# PowerAndController.net
KiCad netlist of a schematic drawn in Altium Designer
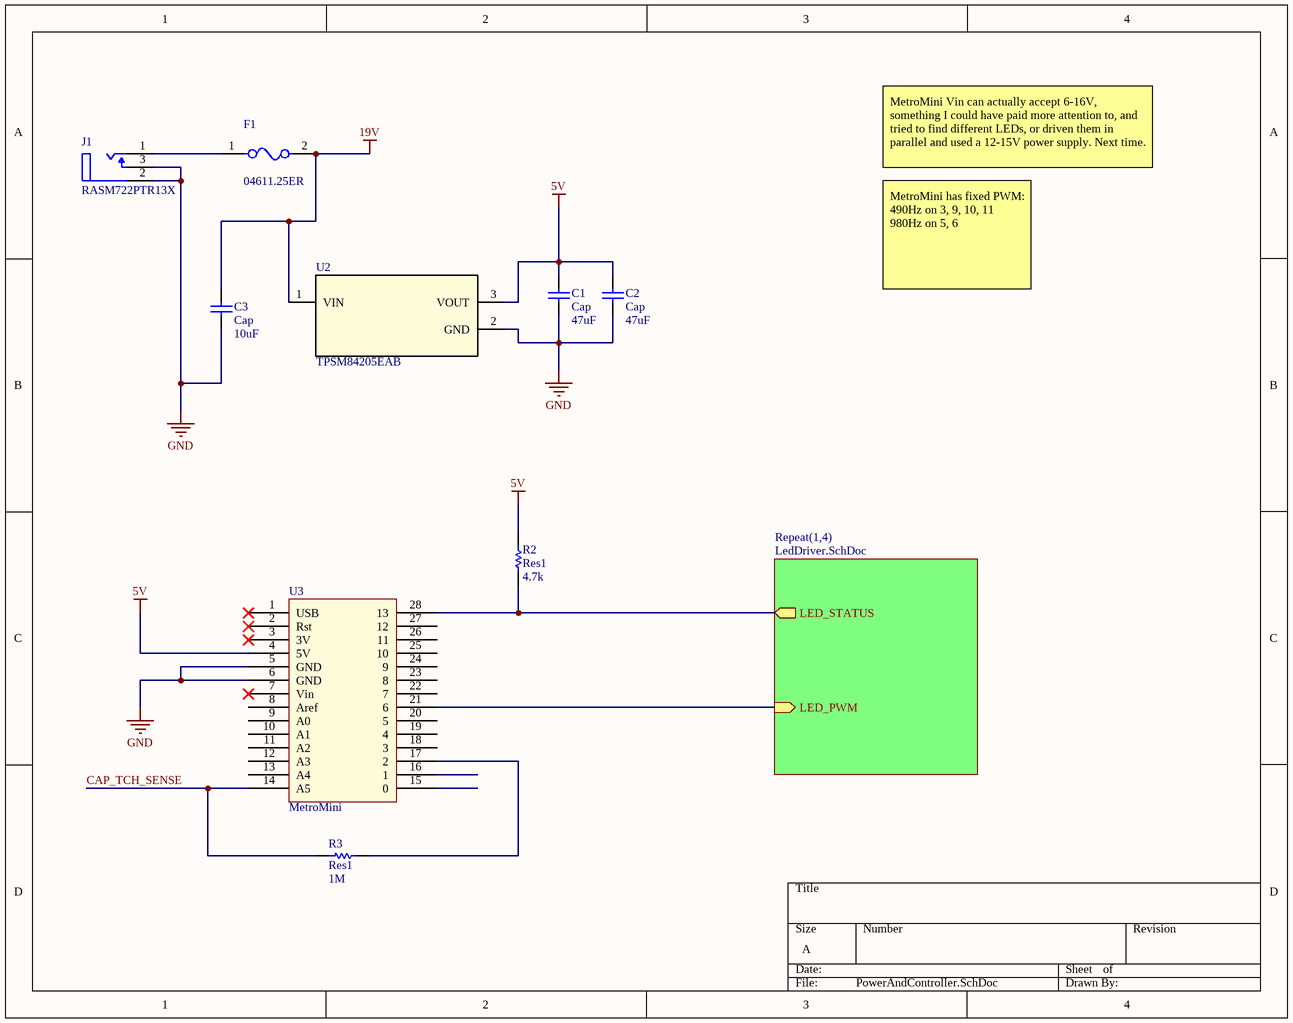
[diagram p0: PowerAndController.SchDoc]

(export (version "E")
  (design (tool "Eeschema 10.0.6"))
  (components
    (comp (ref "C1")
      (value "Cap")
      (footprint "RAD-0.3")
      (description "Capacitor")
      (fields (field (name "ALTIUM_VALUE") "47uF") (field (name "PUBLISHER") "Altium Limited"))
      (libsource (lib "Miscellaneous Devices") (part "Cap"))
    )
    (comp (ref "C2")
      (value "Cap")
      (footprint "RAD-0.3")
      (description "Capacitor")
      (fields (field (name "ALTIUM_VALUE") "47uF") (field (name "PUBLISHER") "Altium Limited"))
      (libsource (lib "Miscellaneous Devices") (part "Cap"))
    )
    (comp (ref "C3")
      (value "Cap")
      (footprint "RAD-0.3")
      (description "Capacitor")
      (fields (field (name "ALTIUM_VALUE") "10uF") (field (name "PUBLISHER") "Altium Limited"))
      (libsource (lib "Miscellaneous Devices") (part "Cap"))
    )
    (comp (ref "F1")
      (value "04611.25ER")
      (footprint "FP-0461-MFG")
      (description "FUSE BRD MNT 1.25A 600VAC/80VDC")
      (fields
        (field (name "OCTOPART") "https://octopart.com/04611.25er-littelfuse-566039")
        (field (name "MANUFACTURER") "Littelfuse Inc")
      )
      (libsource (lib "Altium Content Vault") (part "5bcf9b9f640e542cf0359d10258e979"))
    )
    (comp (ref "J1")
      (value "RASM722PTR13X")
      (footprint "FP-RASM722PTR13X-MFG")
      (description "CONN PWR JACK 2.1X5.5MM SOLDER")
      (libsource (lib "Altium Content Vault") (part "69023cd999ddc70d2a190894d9bbb58"))
    )
    (comp (ref "R2")
      (value "Res1")
      (footprint "AXIAL-0.3")
      (description "Resistor")
      (fields (field (name "ALTIUM_VALUE") "4.7k") (field (name "PUBLISHER") "Altium Limited"))
      (libsource (lib "Miscellaneous Devices") (part "Res1"))
    )
    (comp (ref "R3")
      (value "Res1")
      (footprint "AXIAL-0.3")
      (description "Resistor")
      (fields (field (name "ALTIUM_VALUE") "1M") (field (name "PUBLISHER") "Altium Limited"))
      (libsource (lib "Miscellaneous Devices") (part "Res1"))
    )
    (comp (ref "U2")
      (value "TPSM84205EAB")
      (footprint "EAB0003A")
      (description "No Description Available")
      (fields
        (field (name "PARTNUMBER") "TPSM84205EABT")
        (field (name "MANUFACTURER") "Texas Instruments")
        (field (name "COPYRIGHT") "Copyright (C) 2018 Accelerated Designs. All rights reserved")
      )
      (libsource (lib "2020-09-21_00-30-43") (part "TPSM84205EAB"))
    )
    (comp (ref "U3") (value "MetroMini") (libsource (lib "Main") (part "MetroMini")))
  )
  (nets
    (net (code "1") (name "/CAP_TCH_SENSE") (class "Default")
      (node (ref "R3") (pin "1") (pinfunction "1_1") (pintype "passive"))
      (node (ref "U3") (pin "14") (pinfunction "A5_14") (pintype "passive"))
    )
    (net (code "2") (name "/LED_PWM") (class "Default")
      (node (ref "U3") (pin "21") (pinfunction "6_21") (pintype "passive"))
    )
    (net (code "3") (name "/LED_STATUS") (class "Default")
      (node (ref "R2") (pin "1") (pinfunction "1_1") (pintype "passive"))
      (node (ref "U3") (pin "28") (pinfunction "13_28") (pintype "passive"))
    )
    (net (code "4") (name "5V") (class "Default")
      (node (ref "C1") (pin "2") (pinfunction "2_2") (pintype "passive"))
      (node (ref "C2") (pin "2") (pinfunction "2_2") (pintype "passive"))
      (node (ref "R2") (pin "2") (pinfunction "2_2") (pintype "passive"))
      (node (ref "U2") (pin "3") (pinfunction "VOUT_3") (pintype "power_in"))
      (node (ref "U3") (pin "4") (pinfunction "5V_4") (pintype "passive"))
    )
    (net (code "5") (name "19V") (class "Default")
      (node (ref "C3") (pin "2") (pinfunction "2_2") (pintype "passive"))
      (node (ref "F1") (pin "2") (pinfunction "2_2") (pintype "passive"))
      (node (ref "U2") (pin "1") (pinfunction "VIN_1") (pintype "power_in"))
    )
    (net (code "6") (name "GND") (class "Default")
      (node (ref "C1") (pin "1") (pinfunction "1_1") (pintype "passive"))
      (node (ref "C2") (pin "1") (pinfunction "1_1") (pintype "passive"))
      (node (ref "C3") (pin "1") (pinfunction "1_1") (pintype "passive"))
      (node (ref "J1") (pin "2") (pinfunction "SLEEVE_TERMINAL_2") (pintype "passive"))
      (node (ref "J1") (pin "3") (pinfunction "SHUNT_TERMINAL_3") (pintype "passive"))
      (node (ref "U2") (pin "2") (pinfunction "GND_2") (pintype "power_in"))
      (node (ref "U3") (pin "5") (pinfunction "GND_5") (pintype "passive"))
      (node (ref "U3") (pin "6") (pinfunction "GND_6") (pintype "passive"))
    )
    (net (code "7") (name "Net-(J1-TIP_TERMINAL(CENTER_PIN))") (class "Default")
      (node (ref "F1") (pin "1") (pinfunction "1_1") (pintype "passive"))
      (node (ref "J1") (pin "1") (pinfunction "TIP_TERMINAL(CENTER_PIN)_1") (pintype "passive"))
    )
    (net (code "8") (name "Net-(U3-2)") (class "Default")
      (node (ref "R3") (pin "2") (pinfunction "2_2") (pintype "passive"))
      (node (ref "U3") (pin "17") (pinfunction "2_17") (pintype "passive"))
    )
    (net (code "9") (name "unconnected-(U3-0-Pad15)") (class "Default")
      (node (ref "U3") (pin "15") (pinfunction "0_15") (pintype "passive"))
    )
    (net (code "10") (name "unconnected-(U3-1-Pad16)") (class "Default")
      (node (ref "U3") (pin "16") (pinfunction "1_16") (pintype "passive"))
    )
    (net (code "11") (name "unconnected-(U3-3-Pad18)") (class "Default")
      (node (ref "U3") (pin "18") (pinfunction "3_18") (pintype "passive"))
    )
    (net (code "12") (name "unconnected-(U3-3V-Pad3)") (class "Default")
      (node (ref "U3") (pin "3") (pinfunction "3V_3") (pintype "passive+no_connect"))
    )
    (net (code "13") (name "unconnected-(U3-4-Pad19)") (class "Default")
      (node (ref "U3") (pin "19") (pinfunction "4_19") (pintype "passive"))
    )
    (net (code "14") (name "unconnected-(U3-5-Pad20)") (class "Default")
      (node (ref "U3") (pin "20") (pinfunction "5_20") (pintype "passive"))
    )
    (net (code "15") (name "unconnected-(U3-7-Pad22)") (class "Default")
      (node (ref "U3") (pin "22") (pinfunction "7_22") (pintype "passive"))
    )
    (net (code "16") (name "unconnected-(U3-8-Pad23)") (class "Default")
      (node (ref "U3") (pin "23") (pinfunction "8_23") (pintype "passive"))
    )
    (net (code "17") (name "unconnected-(U3-9-Pad24)") (class "Default")
      (node (ref "U3") (pin "24") (pinfunction "9_24") (pintype "passive"))
    )
    (net (code "18") (name "unconnected-(U3-10-Pad25)") (class "Default")
      (node (ref "U3") (pin "25") (pinfunction "10_25") (pintype "passive"))
    )
    (net (code "19") (name "unconnected-(U3-11-Pad26)") (class "Default")
      (node (ref "U3") (pin "26") (pinfunction "11_26") (pintype "passive"))
    )
    (net (code "20") (name "unconnected-(U3-12-Pad27)") (class "Default")
      (node (ref "U3") (pin "27") (pinfunction "12_27") (pintype "passive"))
    )
    (net (code "21") (name "unconnected-(U3-A0-Pad9)") (class "Default")
      (node (ref "U3") (pin "9") (pinfunction "A0_9") (pintype "passive"))
    )
    (net (code "22") (name "unconnected-(U3-A1-Pad10)") (class "Default")
      (node (ref "U3") (pin "10") (pinfunction "A1_10") (pintype "passive"))
    )
    (net (code "23") (name "unconnected-(U3-A2-Pad11)") (class "Default")
      (node (ref "U3") (pin "11") (pinfunction "A2_11") (pintype "passive"))
    )
    (net (code "24") (name "unconnected-(U3-A3-Pad12)") (class "Default")
      (node (ref "U3") (pin "12") (pinfunction "A3_12") (pintype "passive"))
    )
    (net (code "25") (name "unconnected-(U3-A4-Pad13)") (class "Default")
      (node (ref "U3") (pin "13") (pinfunction "A4_13") (pintype "passive"))
    )
    (net (code "26") (name "unconnected-(U3-Aref-Pad8)") (class "Default")
      (node (ref "U3") (pin "8") (pinfunction "Aref_8") (pintype "passive"))
    )
    (net (code "27") (name "unconnected-(U3-Rst-Pad2)") (class "Default")
      (node (ref "U3") (pin "2") (pinfunction "Rst_2") (pintype "passive+no_connect"))
    )
    (net (code "28") (name "unconnected-(U3-USB-Pad1)") (class "Default")
      (node (ref "U3") (pin "1") (pinfunction "USB_1") (pintype "passive+no_connect"))
    )
    (net (code "29") (name "unconnected-(U3-Vin-Pad7)") (class "Default")
      (node (ref "U3") (pin "7") (pinfunction "Vin_7") (pintype "passive+no_connect"))
    )
  )
)
